# RGB_LED_Control.net
KiCad netlist of a schematic drawn in EasyEDA
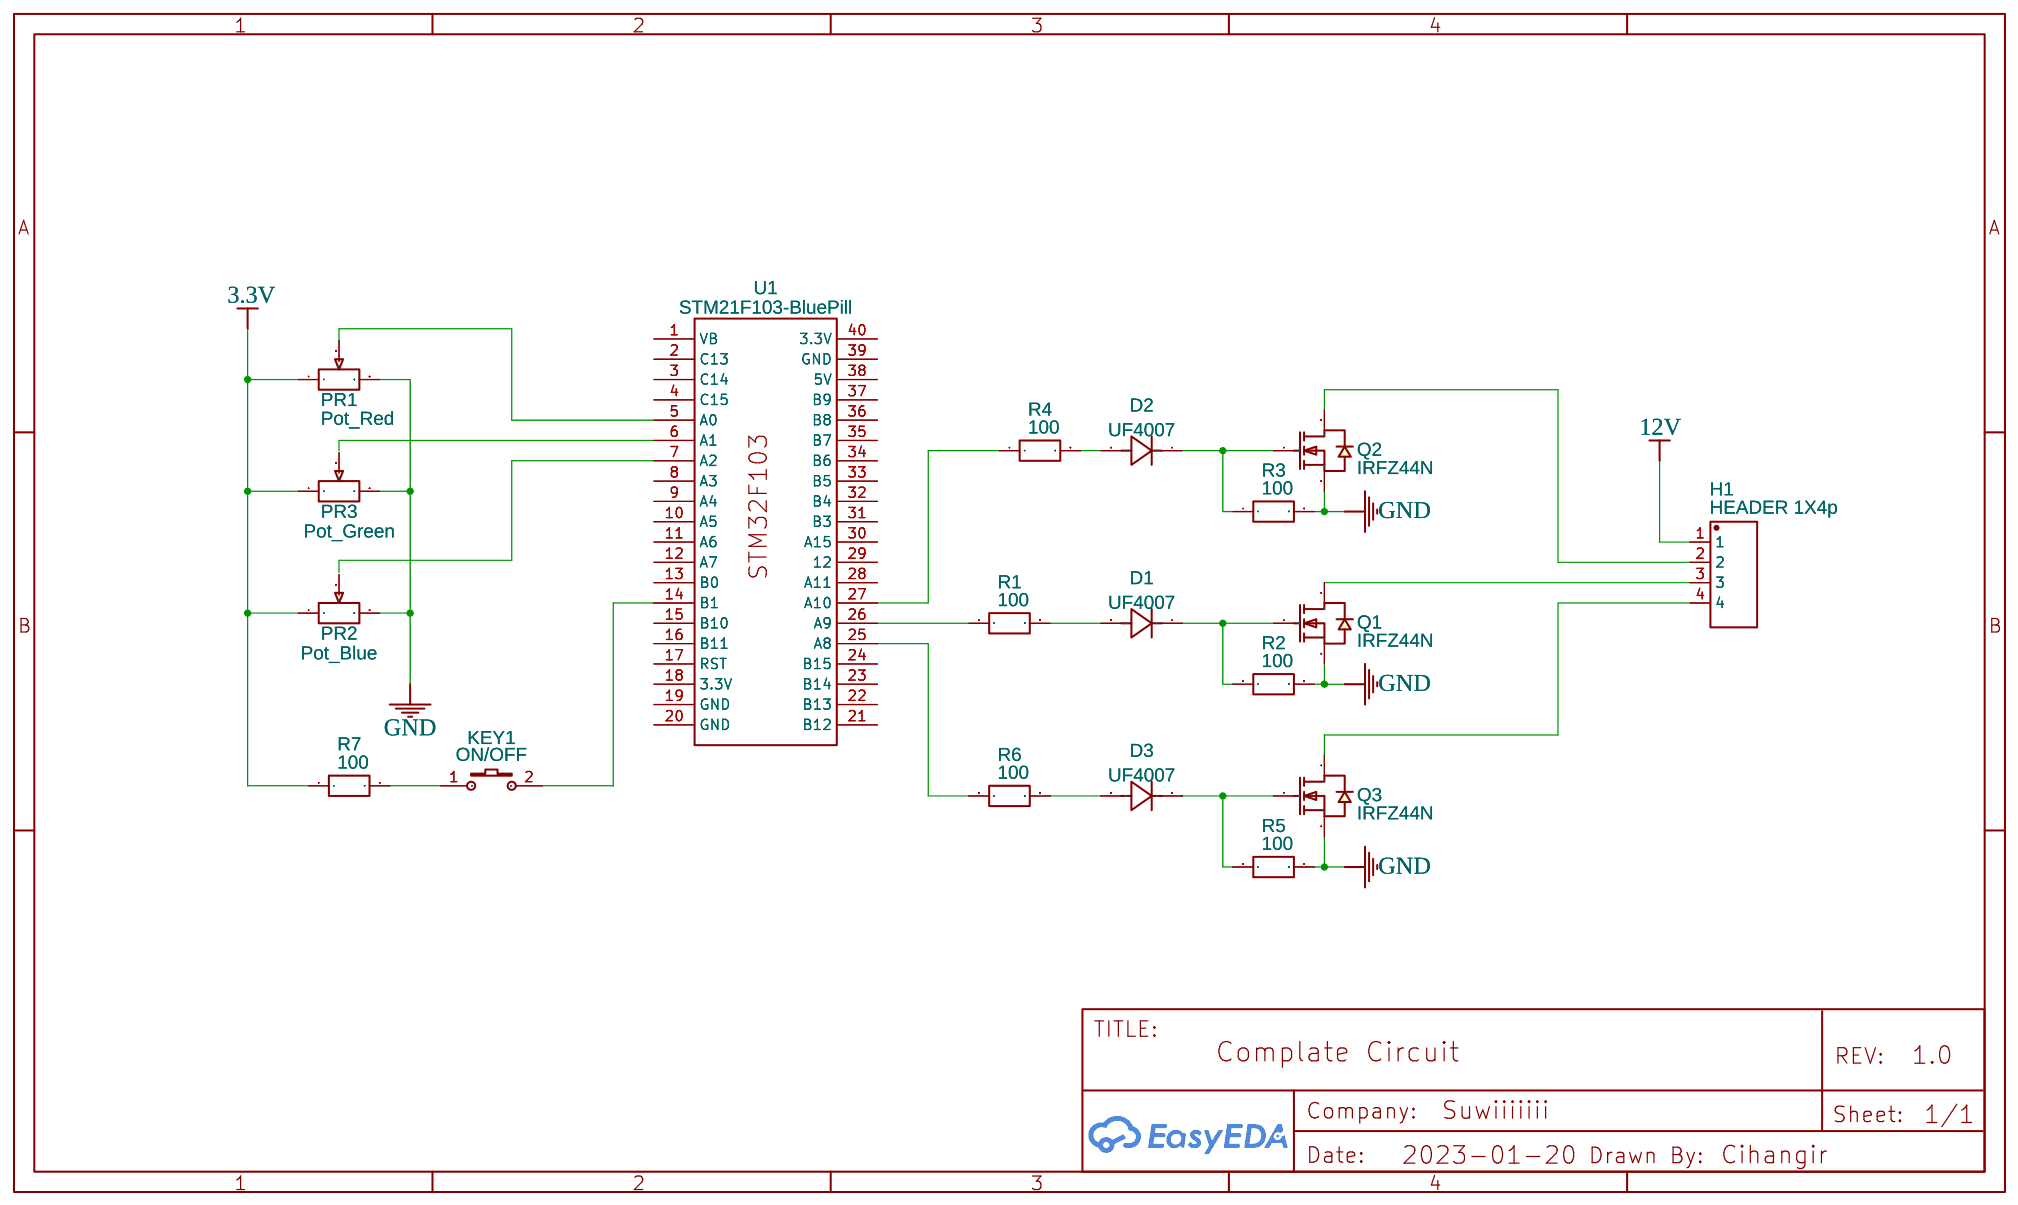
[diagram p0: schematic sheet]

(export (version "E")
  (design (tool "Eeschema 10.0.6"))
  (components
    (comp (ref "D1")
      (value "UF4007")
      (fields (field (name "BOM_Supplier Part") "C9900004719"))
      (libsource (lib "") (part "UF4007"))
    )
    (comp (ref "D2")
      (value "UF4007")
      (fields (field (name "BOM_Supplier Part") "C9900004719"))
      (libsource (lib "") (part "UF4007"))
    )
    (comp (ref "D3")
      (value "UF4007")
      (fields (field (name "BOM_Supplier Part") "C9900004719"))
      (libsource (lib "") (part "UF4007"))
    )
    (comp (ref "H1") (value "HEADER 1X4p") (libsource (lib "") (part "HEADER 1X4p")))
    (comp (ref "KEY1")
      (value "ON/OFF")
      (fields
        (field (name "BOM_Manufacturer Part") "K2-1107ST-A4SW-06")
        (field (name "BOM_Supplier Part") "C118141")
      )
      (libsource (lib "") (part "K2-3.6×6.1_SMD"))
    )
    (comp (ref "PR1")
      (value "Pot_Red")
      (fields
        (field (name "BOM_Manufacturer Part") "Potentiometer WH160-1-104")
        (field (name "BOM_Supplier Part") "C61836")
      )
      (libsource (lib "") (part "Potentiometer copy"))
    )
    (comp (ref "PR2")
      (value "Pot_Blue")
      (fields
        (field (name "BOM_Manufacturer Part") "Potentiometer WH160-1-104")
        (field (name "BOM_Supplier Part") "C61836")
      )
      (libsource (lib "") (part "Potentiometer copy"))
    )
    (comp (ref "PR3")
      (value "Pot_Green")
      (fields
        (field (name "BOM_Manufacturer Part") "Potentiometer WH160-1-104")
        (field (name "BOM_Supplier Part") "C61836")
      )
      (libsource (lib "") (part "Potentiometer copy"))
    )
    (comp (ref "Q1") (value "IRFZ44N") (libsource (lib "") (part "IRFZ44N")))
    (comp (ref "Q2") (value "IRFZ44N") (libsource (lib "") (part "IRFZ44N")))
    (comp (ref "Q3") (value "IRFZ44N") (libsource (lib "") (part "IRFZ44N")))
    (comp (ref "R1") (value "100") (libsource (lib "") (part "R_0603_EU")))
    (comp (ref "R2") (value "100") (libsource (lib "") (part "R_0603_EU")))
    (comp (ref "R3") (value "100") (libsource (lib "") (part "R_0603_EU")))
    (comp (ref "R4") (value "100") (libsource (lib "") (part "R_0603_EU")))
    (comp (ref "R5") (value "100") (libsource (lib "") (part "R_0603_EU")))
    (comp (ref "R6") (value "100") (libsource (lib "") (part "R_0603_EU")))
    (comp (ref "R7") (value "100") (libsource (lib "") (part "R_0603_EU")))
    (comp (ref "U1") (value "STM21F103-BluePill") (libsource (lib "") (part "STM21F103-BluePill")))
  )
  (nets
    (net (code "1") (name "3.3V") (class "Default")
      (node (ref "PR1") (pin "1") (pinfunction "1_1") (pintype "input"))
      (node (ref "PR2") (pin "1") (pinfunction "1_1") (pintype "input"))
      (node (ref "PR3") (pin "1") (pinfunction "1_1") (pintype "input"))
      (node (ref "R7") (pin "1") (pinfunction "1_1") (pintype "unspecified"))
    )
    (net (code "2") (name "12V") (class "Default")
      (node (ref "H1") (pin "1") (pinfunction "1_1") (pintype "unspecified"))
    )
    (net (code "3") (name "GND") (class "Default")
      (node (ref "PR1") (pin "3") (pinfunction "3_3") (pintype "input"))
      (node (ref "PR2") (pin "3") (pinfunction "3_3") (pintype "input"))
      (node (ref "PR3") (pin "3") (pinfunction "3_3") (pintype "input"))
      (node (ref "Q1") (pin "3") (pinfunction "S_3") (pintype "unspecified"))
      (node (ref "Q2") (pin "3") (pinfunction "S_3") (pintype "unspecified"))
      (node (ref "Q3") (pin "3") (pinfunction "S_3") (pintype "unspecified"))
      (node (ref "R2") (pin "2") (pinfunction "2_2") (pintype "unspecified"))
      (node (ref "R3") (pin "2") (pinfunction "2_2") (pintype "unspecified"))
      (node (ref "R5") (pin "2") (pinfunction "2_2") (pintype "unspecified"))
    )
    (net (code "4") (name "Net-(D1-A)") (class "Default")
      (node (ref "D1") (pin "2") (pinfunction "A_2") (pintype "unspecified"))
      (node (ref "R1") (pin "2") (pinfunction "2_2") (pintype "unspecified"))
    )
    (net (code "5") (name "Net-(D1-K)") (class "Default")
      (node (ref "D1") (pin "1") (pinfunction "K_1") (pintype "unspecified"))
      (node (ref "Q1") (pin "1") (pinfunction "G_1") (pintype "unspecified"))
      (node (ref "R2") (pin "1") (pinfunction "1_1") (pintype "unspecified"))
    )
    (net (code "6") (name "Net-(D2-A)") (class "Default")
      (node (ref "D2") (pin "2") (pinfunction "A_2") (pintype "unspecified"))
      (node (ref "R4") (pin "2") (pinfunction "2_2") (pintype "unspecified"))
    )
    (net (code "7") (name "Net-(D2-K)") (class "Default")
      (node (ref "D2") (pin "1") (pinfunction "K_1") (pintype "unspecified"))
      (node (ref "Q2") (pin "1") (pinfunction "G_1") (pintype "unspecified"))
      (node (ref "R3") (pin "1") (pinfunction "1_1") (pintype "unspecified"))
    )
    (net (code "8") (name "Net-(D3-A)") (class "Default")
      (node (ref "D3") (pin "2") (pinfunction "A_2") (pintype "unspecified"))
      (node (ref "R6") (pin "2") (pinfunction "2_2") (pintype "unspecified"))
    )
    (net (code "9") (name "Net-(D3-K)") (class "Default")
      (node (ref "D3") (pin "1") (pinfunction "K_1") (pintype "unspecified"))
      (node (ref "Q3") (pin "1") (pinfunction "G_1") (pintype "unspecified"))
      (node (ref "R5") (pin "1") (pinfunction "1_1") (pintype "unspecified"))
    )
    (net (code "10") (name "Net-(KEY1-Pad1)") (class "Default")
      (node (ref "KEY1") (pin "1") (pinfunction "1_1") (pintype "unspecified"))
      (node (ref "R7") (pin "2") (pinfunction "2_2") (pintype "unspecified"))
    )
    (net (code "11") (name "Net-(Q1-D)") (class "Default")
      (node (ref "H1") (pin "3") (pinfunction "3_3") (pintype "unspecified"))
      (node (ref "Q1") (pin "2") (pinfunction "D_2") (pintype "unspecified"))
    )
    (net (code "12") (name "Net-(Q2-D)") (class "Default")
      (node (ref "H1") (pin "2") (pinfunction "2_2") (pintype "unspecified"))
      (node (ref "Q2") (pin "2") (pinfunction "D_2") (pintype "unspecified"))
    )
    (net (code "13") (name "Net-(Q3-D)") (class "Default")
      (node (ref "H1") (pin "4") (pinfunction "4_4") (pintype "unspecified"))
      (node (ref "Q3") (pin "2") (pinfunction "D_2") (pintype "unspecified"))
    )
    (net (code "14") (name "Net-(U1-A0)") (class "Default")
      (node (ref "PR1") (pin "2") (pinfunction "2_2") (pintype "input"))
      (node (ref "U1") (pin "5") (pinfunction "A0_5") (pintype "unspecified"))
    )
    (net (code "15") (name "Net-(U1-A8)") (class "Default")
      (node (ref "R6") (pin "1") (pinfunction "1_1") (pintype "unspecified"))
      (node (ref "U1") (pin "25") (pinfunction "A8_25") (pintype "unspecified"))
    )
    (net (code "16") (name "Net-(U1-A9)") (class "Default")
      (node (ref "R1") (pin "1") (pinfunction "1_1") (pintype "unspecified"))
      (node (ref "U1") (pin "26") (pinfunction "A9_26") (pintype "unspecified"))
    )
    (net (code "17") (name "Net-(U1-A10)") (class "Default")
      (node (ref "R4") (pin "1") (pinfunction "1_1") (pintype "unspecified"))
      (node (ref "U1") (pin "27") (pinfunction "A10_27") (pintype "unspecified"))
    )
    (net (code "18") (name "Net-(U1-B1)") (class "Default")
      (node (ref "KEY1") (pin "2") (pinfunction "2_2") (pintype "unspecified"))
      (node (ref "U1") (pin "14") (pinfunction "B1_14") (pintype "unspecified"))
    )
    (net (code "19") (name "unconnected-(PR2-Pad2)") (class "Default")
      (node (ref "PR2") (pin "2") (pinfunction "2_2") (pintype "input"))
    )
    (net (code "20") (name "unconnected-(PR3-Pad2)") (class "Default")
      (node (ref "PR3") (pin "2") (pinfunction "2_2") (pintype "input"))
    )
    (net (code "21") (name "unconnected-(U1-3.3V-Pad18)") (class "Default")
      (node (ref "U1") (pin "18") (pinfunction "3.3V_18") (pintype "unspecified"))
    )
    (net (code "22") (name "unconnected-(U1-3.3V-Pad40)") (class "Default")
      (node (ref "U1") (pin "40") (pinfunction "3.3V_40") (pintype "unspecified"))
    )
    (net (code "23") (name "unconnected-(U1-5V-Pad38)") (class "Default")
      (node (ref "U1") (pin "38") (pinfunction "5V_38") (pintype "unspecified"))
    )
    (net (code "24") (name "unconnected-(U1-12-Pad29)") (class "Default")
      (node (ref "U1") (pin "29") (pinfunction "12_29") (pintype "unspecified"))
    )
    (net (code "25") (name "unconnected-(U1-A1-Pad6)") (class "Default")
      (node (ref "U1") (pin "6") (pinfunction "A1_6") (pintype "unspecified"))
    )
    (net (code "26") (name "unconnected-(U1-A2-Pad7)") (class "Default")
      (node (ref "U1") (pin "7") (pinfunction "A2_7") (pintype "unspecified"))
    )
    (net (code "27") (name "unconnected-(U1-A3-Pad8)") (class "Default")
      (node (ref "U1") (pin "8") (pinfunction "A3_8") (pintype "unspecified"))
    )
    (net (code "28") (name "unconnected-(U1-A4-Pad9)") (class "Default")
      (node (ref "U1") (pin "9") (pinfunction "A4_9") (pintype "unspecified"))
    )
    (net (code "29") (name "unconnected-(U1-A5-Pad10)") (class "Default")
      (node (ref "U1") (pin "10") (pinfunction "A5_10") (pintype "unspecified"))
    )
    (net (code "30") (name "unconnected-(U1-A6-Pad11)") (class "Default")
      (node (ref "U1") (pin "11") (pinfunction "A6_11") (pintype "unspecified"))
    )
    (net (code "31") (name "unconnected-(U1-A7-Pad12)") (class "Default")
      (node (ref "U1") (pin "12") (pinfunction "A7_12") (pintype "unspecified"))
    )
    (net (code "32") (name "unconnected-(U1-A11-Pad28)") (class "Default")
      (node (ref "U1") (pin "28") (pinfunction "A11_28") (pintype "unspecified"))
    )
    (net (code "33") (name "unconnected-(U1-A15-Pad30)") (class "Default")
      (node (ref "U1") (pin "30") (pinfunction "A15_30") (pintype "unspecified"))
    )
    (net (code "34") (name "unconnected-(U1-B0-Pad13)") (class "Default")
      (node (ref "U1") (pin "13") (pinfunction "B0_13") (pintype "unspecified"))
    )
    (net (code "35") (name "unconnected-(U1-B3-Pad31)") (class "Default")
      (node (ref "U1") (pin "31") (pinfunction "B3_31") (pintype "unspecified"))
    )
    (net (code "36") (name "unconnected-(U1-B4-Pad32)") (class "Default")
      (node (ref "U1") (pin "32") (pinfunction "B4_32") (pintype "unspecified"))
    )
    (net (code "37") (name "unconnected-(U1-B5-Pad33)") (class "Default")
      (node (ref "U1") (pin "33") (pinfunction "B5_33") (pintype "unspecified"))
    )
    (net (code "38") (name "unconnected-(U1-B6-Pad34)") (class "Default")
      (node (ref "U1") (pin "34") (pinfunction "B6_34") (pintype "unspecified"))
    )
    (net (code "39") (name "unconnected-(U1-B7-Pad35)") (class "Default")
      (node (ref "U1") (pin "35") (pinfunction "B7_35") (pintype "unspecified"))
    )
    (net (code "40") (name "unconnected-(U1-B8-Pad36)") (class "Default")
      (node (ref "U1") (pin "36") (pinfunction "B8_36") (pintype "unspecified"))
    )
    (net (code "41") (name "unconnected-(U1-B9-Pad37)") (class "Default")
      (node (ref "U1") (pin "37") (pinfunction "B9_37") (pintype "unspecified"))
    )
    (net (code "42") (name "unconnected-(U1-B10-Pad15)") (class "Default")
      (node (ref "U1") (pin "15") (pinfunction "B10_15") (pintype "unspecified"))
    )
    (net (code "43") (name "unconnected-(U1-B11-Pad16)") (class "Default")
      (node (ref "U1") (pin "16") (pinfunction "B11_16") (pintype "unspecified"))
    )
    (net (code "44") (name "unconnected-(U1-B12-Pad21)") (class "Default")
      (node (ref "U1") (pin "21") (pinfunction "B12_21") (pintype "unspecified"))
    )
    (net (code "45") (name "unconnected-(U1-B13-Pad22)") (class "Default")
      (node (ref "U1") (pin "22") (pinfunction "B13_22") (pintype "unspecified"))
    )
    (net (code "46") (name "unconnected-(U1-B14-Pad23)") (class "Default")
      (node (ref "U1") (pin "23") (pinfunction "B14_23") (pintype "unspecified"))
    )
    (net (code "47") (name "unconnected-(U1-B15-Pad24)") (class "Default")
      (node (ref "U1") (pin "24") (pinfunction "B15_24") (pintype "unspecified"))
    )
    (net (code "48") (name "unconnected-(U1-C13-Pad2)") (class "Default")
      (node (ref "U1") (pin "2") (pinfunction "C13_2") (pintype "unspecified"))
    )
    (net (code "49") (name "unconnected-(U1-C14-Pad3)") (class "Default")
      (node (ref "U1") (pin "3") (pinfunction "C14_3") (pintype "unspecified"))
    )
    (net (code "50") (name "unconnected-(U1-C15-Pad4)") (class "Default")
      (node (ref "U1") (pin "4") (pinfunction "C15_4") (pintype "unspecified"))
    )
    (net (code "51") (name "unconnected-(U1-GND-Pad19)") (class "Default")
      (node (ref "U1") (pin "19") (pinfunction "GND_19") (pintype "unspecified"))
    )
    (net (code "52") (name "unconnected-(U1-GND-Pad20)") (class "Default")
      (node (ref "U1") (pin "20") (pinfunction "GND_20") (pintype "unspecified"))
    )
    (net (code "53") (name "unconnected-(U1-GND-Pad39)") (class "Default")
      (node (ref "U1") (pin "39") (pinfunction "GND_39") (pintype "unspecified"))
    )
    (net (code "54") (name "unconnected-(U1-RST-Pad17)") (class "Default")
      (node (ref "U1") (pin "17") (pinfunction "RST_17") (pintype "unspecified"))
    )
    (net (code "55") (name "unconnected-(U1-VB-Pad1)") (class "Default")
      (node (ref "U1") (pin "1") (pinfunction "VB_1") (pintype "unspecified"))
    )
  )
)
